# 24V_to_5V_1A_switching_regulator.net
KiCad netlist of a schematic drawn in EAGLE
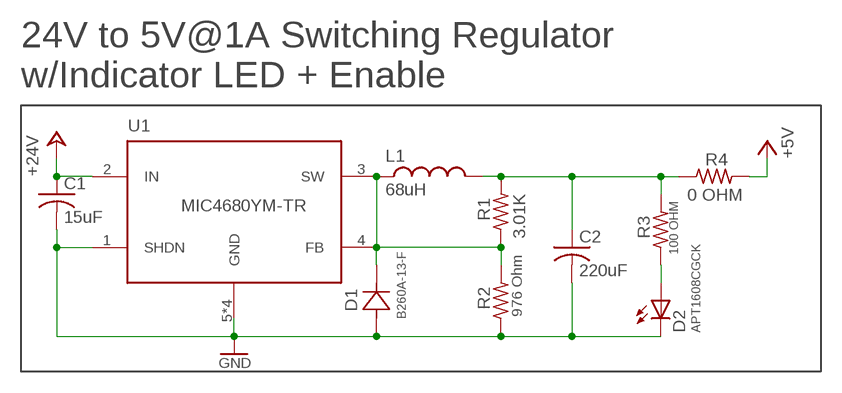
[diagram p0: schematic, sheet 1]

(export (version "E")
  (design (tool "Eeschema 10.0.6"))
  (components
    (comp (ref "C1")
      (value "15uF")
      (footprint "eagle-import:CT7343")
      (libsource (lib "eagle-import") (part "15UF-TPSD156K035R0100"))
    )
    (comp (ref "C2")
      (value "220uF")
      (footprint "eagle-import:CT7343")
      (libsource (lib "eagle-import") (part "220UF-TPSY227K010R0100"))
    )
    (comp (ref "D1")
      (value "B260A-13-F")
      (footprint "eagle-import:SMA")
      (libsource (lib "eagle-import") (part "B260A-13-F"))
    )
    (comp (ref "D2")
      (value "APT1608CGCK")
      (footprint "eagle-import:CHIPLED_0603")
      (libsource (lib "eagle-import") (part "APT1608CGCK"))
    )
    (comp (ref "L1")
      (value "68uH")
      (footprint "eagle-import:UP2B")
      (libsource (lib "eagle-import") (part "68UH-UP2B-680-R"))
    )
    (comp (ref "R1")
      (value "3.01K")
      (footprint "eagle-import:RC0603N")
      (libsource (lib "eagle-import") (part "3.01K-RC0603FR-073K01L"))
    )
    (comp (ref "R2")
      (value "976 Ohm")
      (footprint "eagle-import:RC0603N")
      (libsource (lib "eagle-import") (part "982OHM-RC0603FR-07976RL"))
    )
    (comp (ref "R3")
      (value "100 OHM")
      (footprint "eagle-import:RC0603N")
      (libsource (lib "eagle-import") (part "100OHM-RC0603JR-07100RL"))
    )
    (comp (ref "R4")
      (value "0 OHM")
      (footprint "eagle-import:RC0603N")
      (libsource (lib "eagle-import") (part "0OHM-RC0603JR-070RL"))
    )
    (comp (ref "U1")
      (value "MIC4680YM-TR")
      (footprint "eagle-import:SOIC8")
      (libsource (lib "eagle-import") (part "MIC4680YM-TR"))
    )
  )
  (nets
    (net (code "1") (name "+5V") (class "Default")
      (node (ref "R4") (pin "2") (pinfunction "2_2") (pintype "passive"))
    )
    (net (code "2") (name "+24V") (class "Default")
      (node (ref "C1") (pin "+") (pinfunction "1(+)_+") (pintype "passive"))
      (node (ref "U1") (pin "2") (pinfunction "IN_2") (pintype "bidirectional"))
    )
    (net (code "3") (name "GND") (class "Default")
      (node (ref "C1") (pin "-") (pinfunction "2(-)_-") (pintype "passive"))
      (node (ref "C2") (pin "-") (pinfunction "2(-)_-") (pintype "passive"))
      (node (ref "D1") (pin "2") (pinfunction "21_2") (pintype "passive"))
      (node (ref "D2") (pin "C") (pinfunction "C_C") (pintype "passive"))
      (node (ref "R2") (pin "1") (pinfunction "1_1") (pintype "passive"))
      (node (ref "U1") (pin "1") (pinfunction "SHDN_1") (pintype "bidirectional"))
      (node (ref "U1") (pin "5") (pinfunction "GND_5") (pintype "bidirectional"))
      (node (ref "U1") (pin "6") (pinfunction "GND_6") (pintype "bidirectional"))
      (node (ref "U1") (pin "7") (pinfunction "GND_7") (pintype "bidirectional"))
      (node (ref "U1") (pin "8") (pinfunction "GND_8") (pintype "bidirectional"))
    )
    (net (code "4") (name "Net-(C2-1(+))") (class "Default")
      (node (ref "C2") (pin "+") (pinfunction "1(+)_+") (pintype "passive"))
      (node (ref "L1") (pin "2") (pinfunction "2_2") (pintype "passive"))
      (node (ref "R1") (pin "2") (pinfunction "2_2") (pintype "passive"))
      (node (ref "R3") (pin "2") (pinfunction "2_2") (pintype "passive"))
      (node (ref "R4") (pin "1") (pinfunction "1_1") (pintype "passive"))
    )
    (net (code "5") (name "Net-(D1-12)") (class "Default")
      (node (ref "D1") (pin "1") (pinfunction "12_1") (pintype "passive"))
      (node (ref "L1") (pin "1") (pinfunction "1_1") (pintype "passive"))
      (node (ref "R1") (pin "1") (pinfunction "1_1") (pintype "passive"))
      (node (ref "R2") (pin "2") (pinfunction "2_2") (pintype "passive"))
      (node (ref "U1") (pin "3") (pinfunction "SW_3") (pintype "bidirectional"))
      (node (ref "U1") (pin "4") (pinfunction "FB_4") (pintype "bidirectional"))
    )
    (net (code "6") (name "Net-(D2-PadA)") (class "Default")
      (node (ref "D2") (pin "A") (pinfunction "A_A") (pintype "passive"))
      (node (ref "R3") (pin "1") (pinfunction "1_1") (pintype "passive"))
    )
  )
)
